# AD.net
KiCad netlist of a schematic drawn in Altium Designer
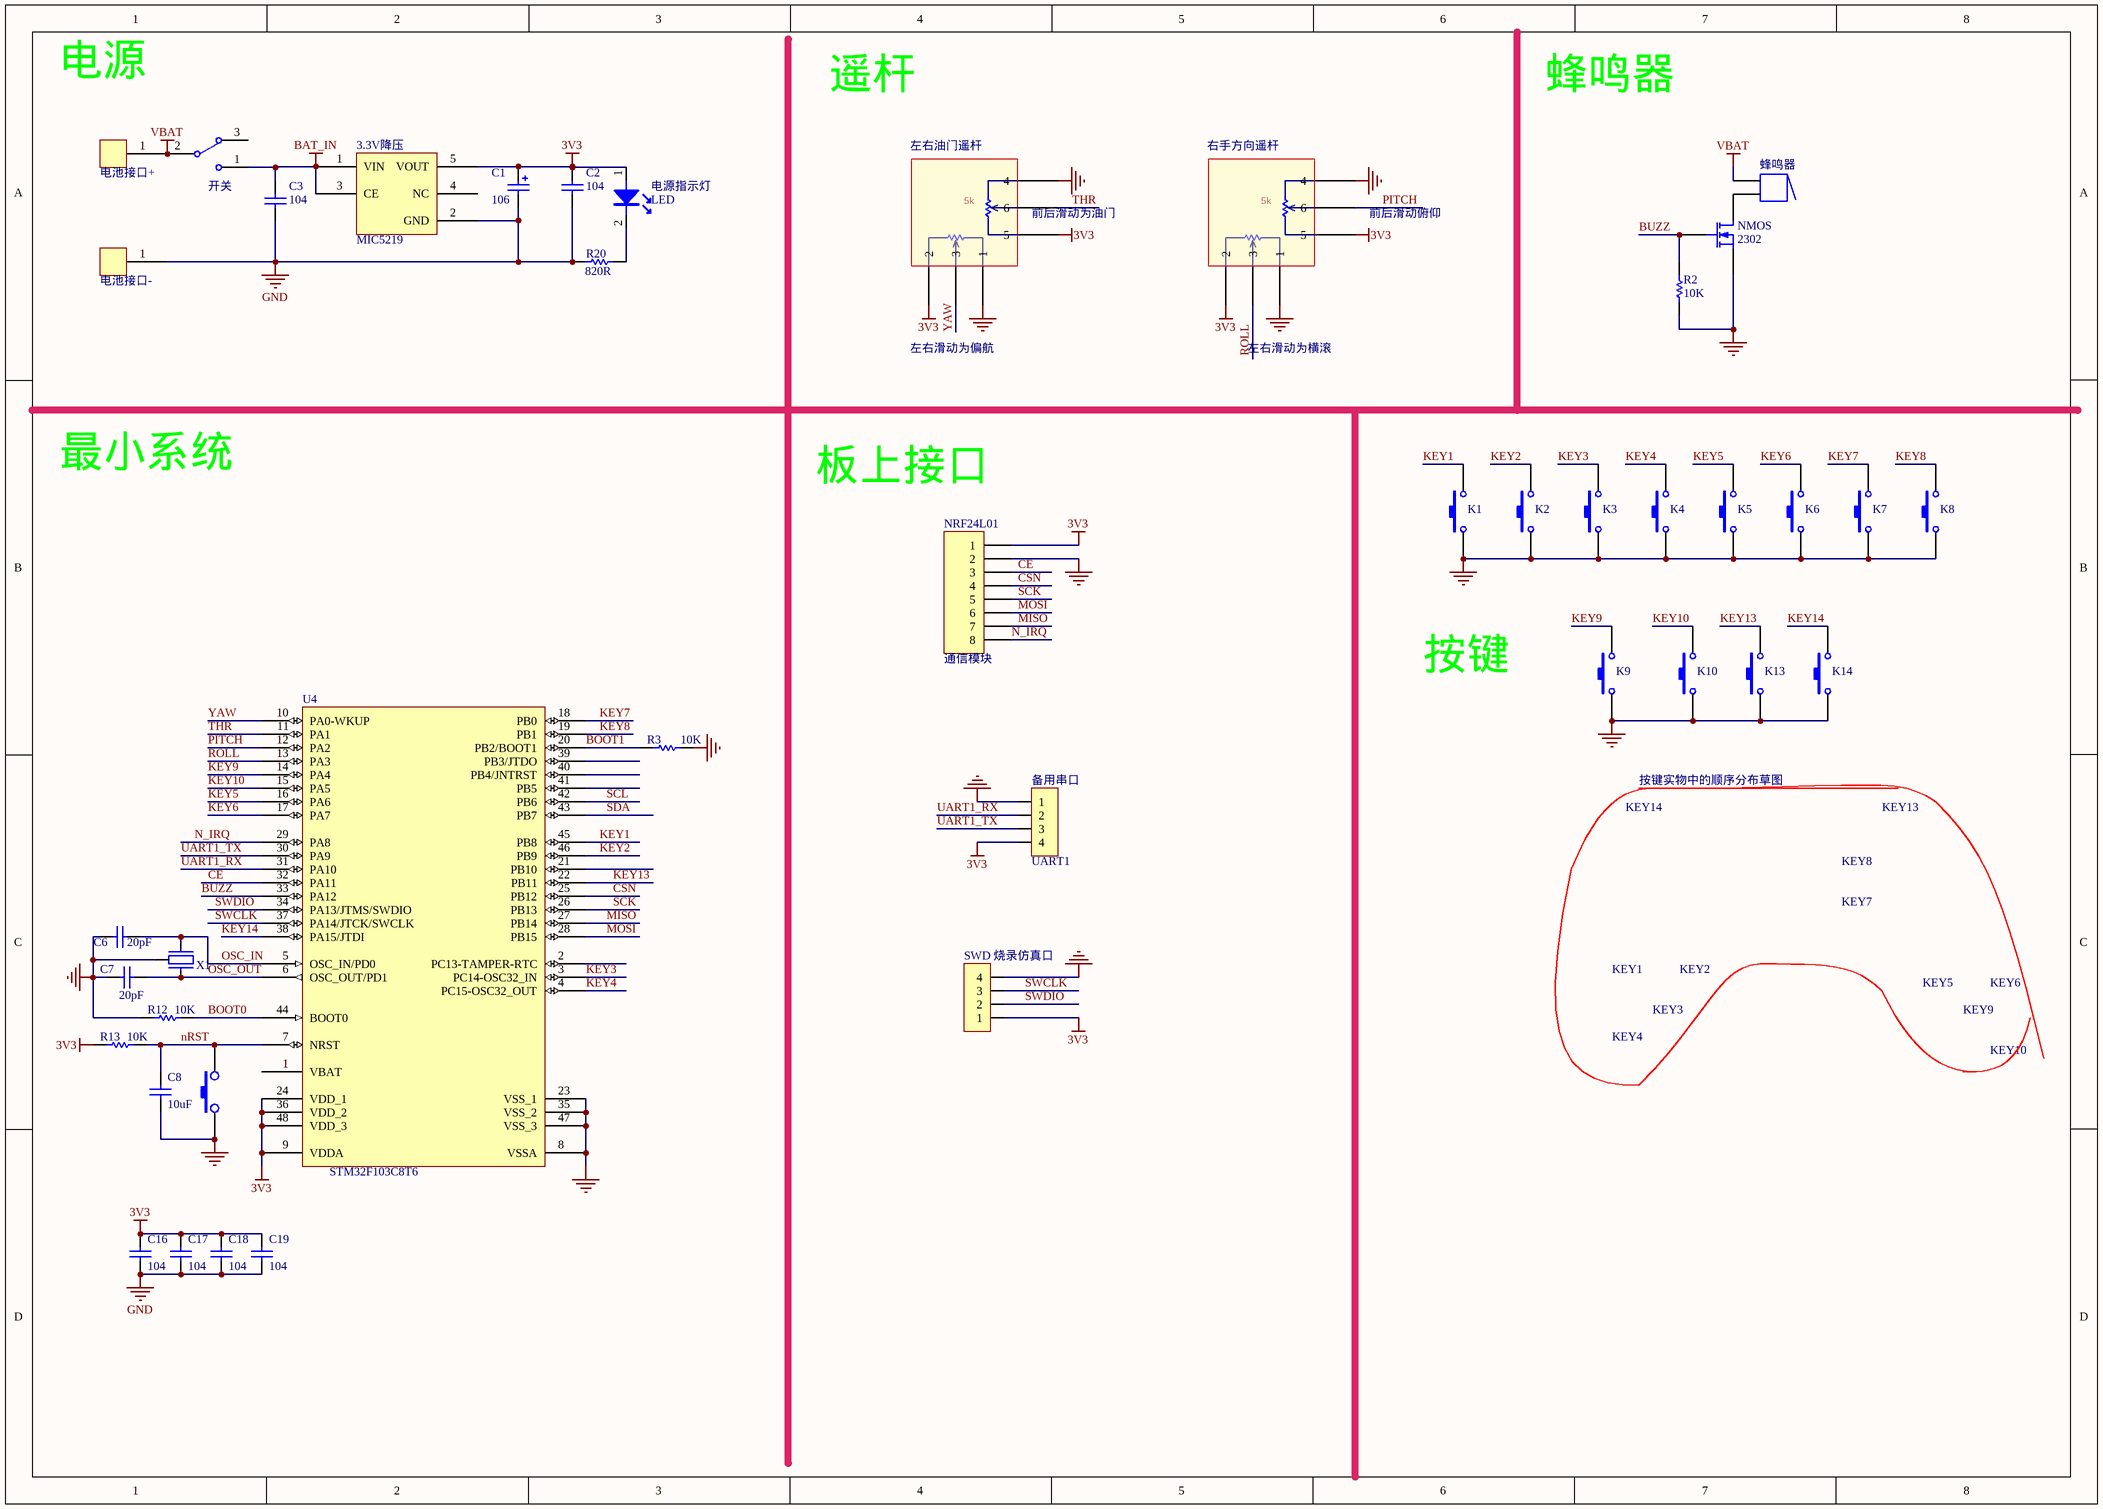
[diagram p0: 遥控原理图（AD打开）.SchDoc]

(export (version "E")
  (design (tool "Eeschema 10.0.6"))
  (components
    (comp (ref "3.3V降压")
      (value "MIC5219")
      (footprint "SOT23-5")
      (libsource (lib "quadrotor") (part "HT7X33"))
    )
    (comp (ref "C1")
      (value "106")
      (footprint "1206")
      (description "Polarized Capacitor (Radial)")
      (fields
        (field (name "VOLTAGE") "16V")
        (field (name "Comment") "Cap Tan A")
        (field (name "PUBLISHER") "Altium Limited")
      )
      (libsource (lib "ChapuIntegratedLibrary") (part "Cap Tan A"))
    )
    (comp (ref "C2")
      (value "104")
      (footprint "1206_C")
      (description "Polarized Capacitor (Radial)")
      (fields (field (name "Comment") "Cap Chip 1206") (field (name "PUBLISHER") "Altium Limited"))
      (libsource (lib "ChapuIntegratedLibrary") (part "Cap Chip 1206"))
    )
    (comp (ref "C3")
      (value "104")
      (footprint "0603_C")
      (description "Polarized Capacitor (Radial)")
      (fields (field (name "Comment") "Cap Chip 1206") (field (name "PUBLISHER") "Altium Limited"))
      (libsource (lib "ChapuIntegratedLibrary") (part "Cap Chip 1206"))
    )
    (comp (ref "C6") (value "20pF") (footprint "0603_C") (libsource (lib "1218迷你四轴工程_1") (part "C0603")))
    (comp (ref "C7") (value "20pF") (footprint "0603_C") (libsource (lib "1218迷你四轴工程_1") (part "C0603")))
    (comp (ref "C8") (value "10uF") (footprint "0603_C") (libsource (lib "1218迷你四轴工程_1") (part "C0603")))
    (comp (ref "C16") (value "104") (footprint "0603_C") (libsource (lib "1218迷你四轴工程_1") (part "C0603")))
    (comp (ref "C17") (value "104") (footprint "0603_C") (libsource (lib "1218迷你四轴工程_1") (part "C0603")))
    (comp (ref "C18") (value "104") (footprint "0603_C") (libsource (lib "1218迷你四轴工程_1") (part "C0603")))
    (comp (ref "C19") (value "104") (footprint "0603_C") (libsource (lib "1218迷你四轴工程_1") (part "C0603")))
    (comp (ref "K1")
      (value "40%（油門上限）")
      (footprint "4脚贴片点动开关")
      (description "Switch")
      (fields (field (name "PUBLISHER") "Altium Limited"))
      (libsource (lib "Miscellaneous Devices") (part "SW-PB"))
    )
    (comp (ref "K2")
      (value "60%")
      (footprint "4脚贴片点动开关")
      (description "Switch")
      (fields (field (name "PUBLISHER") "Altium Limited"))
      (libsource (lib "Miscellaneous Devices") (part "SW-PB"))
    )
    (comp (ref "K3")
      (value "40%（油門上限）")
      (footprint "4脚贴片点动开关")
      (description "Switch")
      (fields (field (name "PUBLISHER") "Altium Limited"))
      (libsource (lib "Miscellaneous Devices") (part "SW-PB"))
    )
    (comp (ref "K4")
      (value "60%")
      (footprint "4脚贴片点动开关")
      (description "Switch")
      (fields (field (name "PUBLISHER") "Altium Limited"))
      (libsource (lib "Miscellaneous Devices") (part "SW-PB"))
    )
    (comp (ref "K5")
      (value "40%（油門上限）")
      (footprint "4脚贴片点动开关")
      (description "Switch")
      (fields (field (name "PUBLISHER") "Altium Limited"))
      (libsource (lib "Miscellaneous Devices") (part "SW-PB"))
    )
    (comp (ref "K6")
      (value "60%")
      (footprint "4脚贴片点动开关")
      (description "Switch")
      (fields (field (name "PUBLISHER") "Altium Limited"))
      (libsource (lib "Miscellaneous Devices") (part "SW-PB"))
    )
    (comp (ref "K7")
      (value "40%（油門上限）")
      (footprint "4脚贴片点动开关")
      (description "Switch")
      (fields (field (name "PUBLISHER") "Altium Limited"))
      (libsource (lib "Miscellaneous Devices") (part "SW-PB"))
    )
    (comp (ref "K8")
      (value "60%")
      (footprint "4脚贴片点动开关")
      (description "Switch")
      (fields (field (name "PUBLISHER") "Altium Limited"))
      (libsource (lib "Miscellaneous Devices") (part "SW-PB"))
    )
    (comp (ref "K9")
      (value "40%（油門上限）")
      (footprint "4脚贴片点动开关")
      (description "Switch")
      (fields (field (name "PUBLISHER") "Altium Limited"))
      (libsource (lib "Miscellaneous Devices") (part "SW-PB"))
    )
    (comp (ref "K10")
      (value "60%")
      (footprint "4脚贴片点动开关")
      (description "Switch")
      (fields (field (name "PUBLISHER") "Altium Limited"))
      (libsource (lib "Miscellaneous Devices") (part "SW-PB"))
    )
    (comp (ref "K13")
      (value "40%（油門上限）")
      (footprint "侧贴侧按点动开关")
      (description "Switch")
      (fields (field (name "PUBLISHER") "Altium Limited"))
      (libsource (lib "Miscellaneous Devices") (part "SW-PB"))
    )
    (comp (ref "K14")
      (value "60%")
      (footprint "侧贴侧按点动开关")
      (description "Switch")
      (fields (field (name "PUBLISHER") "Altium Limited"))
      (libsource (lib "Miscellaneous Devices") (part "SW-PB"))
    )
    (comp (ref "NMOS")
      (value "2302")
      (footprint "SOT-23-3")
      (description "N-Channel MOSFET")
      (fields (field (name "PUBLISHER") "Altium Limited"))
      (libsource (lib "Miscellaneous Devices") (part "MOSFET-N"))
    )
    (comp (ref "NRF24L01")
      (value "通信模块")
      (footprint "HDR1X8")
      (description "Header, 8-Pin")
      (fields (field (name "PUBLISHER") "Altium Limited"))
      (libsource (lib "Miscellaneous Connectors") (part "Header 8"))
    )
    (comp (ref "R2")
      (value "10K")
      (footprint "0603_R")
      (description "Resistor")
      (fields (field (name "Comment") "222") (field (name "PUBLISHER") "Altium Limited"))
      (libsource (lib "Miscellaneous Devices") (part "Res1"))
    )
    (comp (ref "R3")
      (value "10K")
      (footprint "0603_R")
      (description "Resistor")
      (fields (field (name "Comment") "Res1") (field (name "PUBLISHER") "Altium Limited"))
      (libsource (lib "Miscellaneous Devices") (part "Res1"))
    )
    (comp (ref "R12")
      (value "10K")
      (footprint "0603_R")
      (description "Resistor")
      (fields (field (name "Comment") "Res1") (field (name "PUBLISHER") "Altium Limited"))
      (libsource (lib "Miscellaneous Devices") (part "Res1"))
    )
    (comp (ref "R13")
      (value "10K")
      (footprint "0603_R")
      (description "Resistor")
      (fields (field (name "Comment") "Res1") (field (name "PUBLISHER") "Altium Limited"))
      (libsource (lib "Miscellaneous Devices") (part "Res1"))
    )
    (comp (ref "R20")
      (value "820R")
      (footprint "0603_R")
      (description "Resistor")
      (fields (field (name "Comment") "222") (field (name "PUBLISHER") "Altium Limited"))
      (libsource (lib "Miscellaneous Devices") (part "Res1"))
    )
    (comp (ref "REST1") (value "SW-PB") (footprint "SW-2") (libsource (lib "SW开关") (part "SW-PB")))
    (comp (ref "SWD 烧录仿真口")
      (value "SWD")
      (footprint "1.27侧卧表贴")
      (description "Header, 4-Pin, Right Angle")
      (fields (field (name "PUBLISHER") "Altium Limited"))
      (libsource (lib "linch051") (part "Header 4H"))
    )
    (comp (ref "U4")
      (value "STM32F103C8T6")
      (footprint "LQFP48")
      (libsource (lib "微型四轴") (part "STM32F103C8T6"))
    )
    (comp (ref "X1") (value "XTAL_SMT") (footprint "村田陶瓷晶振") (libsource (lib "dx原理图库") (part "XTAL_SMT")))
    (comp (ref "右手方向遥杆") (value "摇杆") (footprint "遥控电位器") (libsource (lib "开源小遥控") (part "摇杆")))
    (comp (ref "备用串口")
      (value "UART1")
      (footprint "1.27侧卧表贴")
      (description "Header, 4-Pin, Right Angle")
      (fields (field (name "PUBLISHER") "Altium Limited"))
      (libsource (lib "") (part "Header 4H_1"))
    )
    (comp (ref "左右油门遥杆") (value "摇杆") (footprint "遥控电位器") (libsource (lib "开源小遥控") (part "摇杆")))
    (comp (ref "开关")
      (value "SW-SPDT")
      (footprint "SW-5")
      (description "SPDT Subminiature Toggle Switch, Right Angle Mounting, Vertical Actuation")
      (fields (field (name "PUBLISHER") "Altium Limited"))
      (libsource (lib "Miscellaneous Devices") (part "SW-SPDT"))
    )
    (comp (ref "电池接口+") (value "Header 1") (footprint "BAT") (libsource (lib "quadrotor") (part "Header 1")))
    (comp (ref "电池接口-") (value "Header 1") (footprint "BAT") (libsource (lib "quadrotor") (part "Header 1")))
    (comp (ref "电源指示灯") (value "LED") (footprint "0603_LED") (libsource (lib "1218迷你四轴工程_1") (part "LED")))
    (comp (ref "蜂鸣器")
      (value "Buzzer")
      (footprint "蜂鸣器9mm")
      (description "Magnetic Transducer Buzzer")
      (fields (field (name "PUBLISHER") "Altium Limited"))
      (libsource (lib "PCB_Project1") (part "Buzzer"))
    )
  )
  (nets
    (net (code "1") (name "/BOOT0") (class "Default")
      (node (ref "R12") (pin "1") (pinfunction "1_1") (pintype "passive"))
      (node (ref "U4") (pin "44") (pinfunction "BOOT0_44") (pintype "input"))
    )
    (net (code "2") (name "/BOOT1") (class "Default")
      (node (ref "R3") (pin "2") (pinfunction "2_2") (pintype "passive"))
      (node (ref "U4") (pin "20") (pinfunction "PB2/BOOT1_20") (pintype "bidirectional"))
    )
    (net (code "3") (name "/BUZZ") (class "Default")
      (node (ref "NMOS") (pin "2") (pinfunction "G_2") (pintype "passive"))
      (node (ref "R2") (pin "1") (pinfunction "1_1") (pintype "passive"))
      (node (ref "U4") (pin "33") (pinfunction "PA12_33") (pintype "bidirectional"))
    )
    (net (code "4") (name "/CE") (class "Default")
      (node (ref "NRF24L01") (pin "3") (pinfunction "3_3") (pintype "passive"))
      (node (ref "U4") (pin "32") (pinfunction "PA11_32") (pintype "bidirectional"))
    )
    (net (code "5") (name "/CSN") (class "Default")
      (node (ref "NRF24L01") (pin "4") (pinfunction "4_4") (pintype "passive"))
      (node (ref "U4") (pin "25") (pinfunction "PB12_25") (pintype "bidirectional"))
    )
    (net (code "6") (name "/KEY1") (class "Default")
      (node (ref "K1") (pin "2") (pinfunction "2_2") (pintype "passive"))
      (node (ref "U4") (pin "45") (pinfunction "PB8_45") (pintype "bidirectional"))
    )
    (net (code "7") (name "/KEY2") (class "Default")
      (node (ref "K2") (pin "2") (pinfunction "2_2") (pintype "passive"))
      (node (ref "U4") (pin "46") (pinfunction "PB9_46") (pintype "bidirectional"))
    )
    (net (code "8") (name "/KEY3") (class "Default")
      (node (ref "K3") (pin "2") (pinfunction "2_2") (pintype "passive"))
      (node (ref "U4") (pin "3") (pinfunction "PC14-OSC32_IN_3") (pintype "bidirectional"))
    )
    (net (code "9") (name "/KEY4") (class "Default")
      (node (ref "K4") (pin "2") (pinfunction "2_2") (pintype "passive"))
      (node (ref "U4") (pin "4") (pinfunction "PC15-OSC32_OUT_4") (pintype "bidirectional"))
    )
    (net (code "10") (name "/KEY5") (class "Default")
      (node (ref "K5") (pin "2") (pinfunction "2_2") (pintype "passive"))
      (node (ref "U4") (pin "16") (pinfunction "PA6_16") (pintype "bidirectional"))
    )
    (net (code "11") (name "/KEY6") (class "Default")
      (node (ref "K6") (pin "2") (pinfunction "2_2") (pintype "passive"))
      (node (ref "U4") (pin "17") (pinfunction "PA7_17") (pintype "bidirectional"))
    )
    (net (code "12") (name "/KEY7") (class "Default")
      (node (ref "K7") (pin "2") (pinfunction "2_2") (pintype "passive"))
      (node (ref "U4") (pin "18") (pinfunction "PB0_18") (pintype "bidirectional"))
    )
    (net (code "13") (name "/KEY8") (class "Default")
      (node (ref "K8") (pin "2") (pinfunction "2_2") (pintype "passive"))
      (node (ref "U4") (pin "19") (pinfunction "PB1_19") (pintype "bidirectional"))
    )
    (net (code "14") (name "/KEY9") (class "Default")
      (node (ref "K9") (pin "2") (pinfunction "2_2") (pintype "passive"))
      (node (ref "U4") (pin "14") (pinfunction "PA4_14") (pintype "bidirectional"))
    )
    (net (code "15") (name "/KEY10") (class "Default")
      (node (ref "K10") (pin "2") (pinfunction "2_2") (pintype "passive"))
      (node (ref "U4") (pin "15") (pinfunction "PA5_15") (pintype "bidirectional"))
    )
    (net (code "16") (name "/KEY13") (class "Default")
      (node (ref "K13") (pin "2") (pinfunction "2_2") (pintype "passive"))
      (node (ref "U4") (pin "22") (pinfunction "PB11_22") (pintype "bidirectional"))
    )
    (net (code "17") (name "/KEY14") (class "Default")
      (node (ref "K14") (pin "2") (pinfunction "2_2") (pintype "passive"))
      (node (ref "U4") (pin "38") (pinfunction "PA15/JTDI_38") (pintype "bidirectional"))
    )
    (net (code "18") (name "/MISO") (class "Default")
      (node (ref "NRF24L01") (pin "7") (pinfunction "7_7") (pintype "passive"))
      (node (ref "U4") (pin "27") (pinfunction "PB14_27") (pintype "bidirectional"))
    )
    (net (code "19") (name "/MOSI") (class "Default")
      (node (ref "NRF24L01") (pin "6") (pinfunction "6_6") (pintype "passive"))
      (node (ref "U4") (pin "28") (pinfunction "PB15_28") (pintype "bidirectional"))
    )
    (net (code "20") (name "/N_IRQ") (class "Default")
      (node (ref "NRF24L01") (pin "8") (pinfunction "8_8") (pintype "passive"))
      (node (ref "U4") (pin "29") (pinfunction "PA8_29") (pintype "bidirectional"))
    )
    (net (code "21") (name "/OSC_IN") (class "Default")
      (node (ref "C6") (pin "1") (pinfunction "1_1") (pintype "passive"))
      (node (ref "U4") (pin "5") (pinfunction "OSC_IN/PD0_5") (pintype "input"))
      (node (ref "X1") (pin "2") (pintype "passive"))
    )
    (net (code "22") (name "/OSC_OUT") (class "Default")
      (node (ref "C7") (pin "1") (pinfunction "1_1") (pintype "passive"))
      (node (ref "U4") (pin "6") (pinfunction "OSC_OUT/PD1_6") (pintype "output"))
      (node (ref "X1") (pin "1") (pintype "passive"))
    )
    (net (code "23") (name "/PITCH") (class "Default")
      (node (ref "U4") (pin "12") (pinfunction "PA2_12") (pintype "bidirectional"))
      (node (ref "右手方向遥杆") (pin "6") (pinfunction "6_6") (pintype "passive"))
    )
    (net (code "24") (name "/ROLL") (class "Default")
      (node (ref "U4") (pin "13") (pinfunction "PA3_13") (pintype "bidirectional"))
      (node (ref "右手方向遥杆") (pin "3") (pinfunction "3_3") (pintype "passive"))
    )
    (net (code "25") (name "/SCK") (class "Default")
      (node (ref "NRF24L01") (pin "5") (pinfunction "5_5") (pintype "passive"))
      (node (ref "U4") (pin "26") (pinfunction "PB13_26") (pintype "bidirectional"))
    )
    (net (code "26") (name "/SCL") (class "Default")
      (node (ref "U4") (pin "42") (pinfunction "PB6_42") (pintype "bidirectional"))
    )
    (net (code "27") (name "/SDA") (class "Default")
      (node (ref "U4") (pin "43") (pinfunction "PB7_43") (pintype "bidirectional"))
    )
    (net (code "28") (name "/SWCLK") (class "Default")
      (node (ref "SWD 烧录仿真口") (pin "3") (pinfunction "3_3") (pintype "passive"))
      (node (ref "U4") (pin "37") (pinfunction "PA14/JTCK/SWCLK_37") (pintype "bidirectional"))
    )
    (net (code "29") (name "/SWDIO") (class "Default")
      (node (ref "SWD 烧录仿真口") (pin "2") (pinfunction "2_2") (pintype "passive"))
      (node (ref "U4") (pin "34") (pinfunction "PA13/JTMS/SWDIO_34") (pintype "bidirectional"))
    )
    (net (code "30") (name "/THR") (class "Default")
      (node (ref "U4") (pin "11") (pinfunction "PA1_11") (pintype "bidirectional"))
      (node (ref "左右油门遥杆") (pin "6") (pinfunction "6_6") (pintype "passive"))
    )
    (net (code "31") (name "/UART1_RX") (class "Default")
      (node (ref "U4") (pin "31") (pinfunction "PA10_31") (pintype "bidirectional"))
      (node (ref "备用串口") (pin "2") (pinfunction "2_2") (pintype "passive"))
    )
    (net (code "32") (name "/UART1_TX") (class "Default")
      (node (ref "U4") (pin "30") (pinfunction "PA9_30") (pintype "bidirectional"))
      (node (ref "备用串口") (pin "3") (pinfunction "3_3") (pintype "passive"))
    )
    (net (code "33") (name "/YAW") (class "Default")
      (node (ref "U4") (pin "10") (pinfunction "PA0-WKUP_10") (pintype "bidirectional"))
      (node (ref "左右油门遥杆") (pin "3") (pinfunction "3_3") (pintype "passive"))
    )
    (net (code "34") (name "/nRST") (class "Default")
      (node (ref "C8") (pin "1") (pinfunction "1_1") (pintype "passive"))
      (node (ref "R13") (pin "1") (pinfunction "1_1") (pintype "passive"))
      (node (ref "REST1") (pin "2") (pinfunction "2_2") (pintype "passive"))
      (node (ref "U4") (pin "7") (pinfunction "NRST_7") (pintype "bidirectional"))
    )
    (net (code "35") (name "3V3") (class "Default")
      (node (ref "3.3V降压") (pin "5") (pinfunction "VOUT_5") (pintype "passive"))
      (node (ref "C1") (pin "2") (pinfunction "1_2") (pintype "passive"))
      (node (ref "C16") (pin "1") (pinfunction "1_1") (pintype "passive"))
      (node (ref "C17") (pin "1") (pinfunction "1_1") (pintype "passive"))
      (node (ref "C18") (pin "1") (pinfunction "1_1") (pintype "passive"))
      (node (ref "C19") (pin "1") (pinfunction "1_1") (pintype "passive"))
      (node (ref "C2") (pin "1") (pinfunction "1_1") (pintype "passive"))
      (node (ref "NRF24L01") (pin "1") (pinfunction "1_1") (pintype "passive"))
      (node (ref "R13") (pin "2") (pinfunction "2_2") (pintype "passive"))
      (node (ref "SWD 烧录仿真口") (pin "1") (pinfunction "1_1") (pintype "passive"))
      (node (ref "U4") (pin "24") (pinfunction "VDD_1_24") (pintype "power_in"))
      (node (ref "U4") (pin "36") (pinfunction "VDD_2_36") (pintype "power_in"))
      (node (ref "U4") (pin "48") (pinfunction "VDD_3_48") (pintype "power_in"))
      (node (ref "U4") (pin "9") (pinfunction "VDDA_9") (pintype "power_in"))
      (node (ref "右手方向遥杆") (pin "2") (pinfunction "2_2") (pintype "passive"))
      (node (ref "右手方向遥杆") (pin "5") (pinfunction "5_5") (pintype "passive"))
      (node (ref "备用串口") (pin "4") (pinfunction "4_4") (pintype "passive"))
      (node (ref "左右油门遥杆") (pin "2") (pinfunction "2_2") (pintype "passive"))
      (node (ref "左右油门遥杆") (pin "5") (pinfunction "5_5") (pintype "passive"))
      (node (ref "电源指示灯") (pin "1") (pinfunction "1_1") (pintype "passive"))
    )
    (net (code "36") (name "BAT_IN") (class "Default")
      (node (ref "3.3V降压") (pin "1") (pinfunction "VIN_1") (pintype "passive"))
      (node (ref "3.3V降压") (pin "3") (pinfunction "CE_3") (pintype "passive"))
      (node (ref "C3") (pin "1") (pinfunction "1_1") (pintype "passive"))
      (node (ref "开关") (pin "1") (pinfunction "1_1") (pintype "passive"))
    )
    (net (code "37") (name "GND") (class "Default")
      (node (ref "3.3V降压") (pin "2") (pinfunction "GND_2") (pintype "passive"))
      (node (ref "C1") (pin "1") (pinfunction "2_1") (pintype "passive"))
      (node (ref "C16") (pin "2") (pinfunction "2_2") (pintype "passive"))
      (node (ref "C17") (pin "2") (pinfunction "2_2") (pintype "passive"))
      (node (ref "C18") (pin "2") (pinfunction "2_2") (pintype "passive"))
      (node (ref "C19") (pin "2") (pinfunction "2_2") (pintype "passive"))
      (node (ref "C2") (pin "2") (pinfunction "2_2") (pintype "passive"))
      (node (ref "C3") (pin "2") (pinfunction "2_2") (pintype "passive"))
      (node (ref "C6") (pin "2") (pinfunction "2_2") (pintype "passive"))
      (node (ref "C7") (pin "2") (pinfunction "2_2") (pintype "passive"))
      (node (ref "C8") (pin "2") (pinfunction "2_2") (pintype "passive"))
      (node (ref "K1") (pin "1") (pinfunction "1_1") (pintype "passive"))
      (node (ref "K10") (pin "1") (pinfunction "1_1") (pintype "passive"))
      (node (ref "K13") (pin "1") (pinfunction "1_1") (pintype "passive"))
      (node (ref "K14") (pin "1") (pinfunction "1_1") (pintype "passive"))
      (node (ref "K2") (pin "1") (pinfunction "1_1") (pintype "passive"))
      (node (ref "K3") (pin "1") (pinfunction "1_1") (pintype "passive"))
      (node (ref "K4") (pin "1") (pinfunction "1_1") (pintype "passive"))
      (node (ref "K5") (pin "1") (pinfunction "1_1") (pintype "passive"))
      (node (ref "K6") (pin "1") (pinfunction "1_1") (pintype "passive"))
      (node (ref "K7") (pin "1") (pinfunction "1_1") (pintype "passive"))
      (node (ref "K8") (pin "1") (pinfunction "1_1") (pintype "passive"))
      (node (ref "K9") (pin "1") (pinfunction "1_1") (pintype "passive"))
      (node (ref "NMOS") (pin "3") (pinfunction "S_3") (pintype "passive"))
      (node (ref "NRF24L01") (pin "2") (pinfunction "2_2") (pintype "passive"))
      (node (ref "R12") (pin "2") (pinfunction "2_2") (pintype "passive"))
      (node (ref "R2") (pin "2") (pinfunction "2_2") (pintype "passive"))
      (node (ref "R20") (pin "1") (pinfunction "1_1") (pintype "passive"))
      (node (ref "R3") (pin "1") (pinfunction "1_1") (pintype "passive"))
      (node (ref "REST1") (pin "1") (pinfunction "1_1") (pintype "passive"))
      (node (ref "SWD 烧录仿真口") (pin "4") (pinfunction "4_4") (pintype "passive"))
      (node (ref "U4") (pin "23") (pinfunction "VSS_1_23") (pintype "power_in"))
      (node (ref "U4") (pin "35") (pinfunction "VSS_2_35") (pintype "power_in"))
      (node (ref "U4") (pin "47") (pinfunction "VSS_3_47") (pintype "power_in"))
      (node (ref "U4") (pin "8") (pinfunction "VSSA_8") (pintype "power_in"))
      (node (ref "X1") (pin "0") (pinfunction "0_0") (pintype "passive"))
      (node (ref "右手方向遥杆") (pin "1") (pinfunction "1_1") (pintype "passive"))
      (node (ref "右手方向遥杆") (pin "4") (pinfunction "4_4") (pintype "passive"))
      (node (ref "备用串口") (pin "1") (pinfunction "1_1") (pintype "passive"))
      (node (ref "左右油门遥杆") (pin "1") (pinfunction "1_1") (pintype "passive"))
      (node (ref "左右油门遥杆") (pin "4") (pinfunction "4_4") (pintype "passive"))
      (node (ref "电池接口-") (pin "1") (pintype "passive"))
    )
    (net (code "38") (name "Net-(NMOS-D)") (class "Default")
      (node (ref "NMOS") (pin "1") (pinfunction "D_1") (pintype "passive"))
      (node (ref "蜂鸣器") (pin "1") (pinfunction "1_1") (pintype "passive"))
    )
    (net (code "39") (name "Net-(R20-Pad2)") (class "Default")
      (node (ref "R20") (pin "2") (pinfunction "2_2") (pintype "passive"))
      (node (ref "电源指示灯") (pin "2") (pinfunction "2_2") (pintype "passive"))
    )
    (net (code "40") (name "VBAT") (class "Default")
      (node (ref "开关") (pin "2") (pinfunction "2_2") (pintype "passive"))
      (node (ref "电池接口+") (pin "1") (pintype "passive"))
      (node (ref "蜂鸣器") (pin "2") (pinfunction "2_2") (pintype "passive"))
    )
    (net (code "41") (name "unconnected-(3.3V降压-NC-Pad4)") (class "Default")
      (node (ref "3.3V降压") (pin "4") (pinfunction "NC_4") (pintype "passive"))
    )
    (net (code "42") (name "unconnected-(U4-PB3{slash}JTDO-Pad39)") (class "Default")
      (node (ref "U4") (pin "39") (pinfunction "PB3/JTDO_39") (pintype "bidirectional"))
    )
    (net (code "43") (name "unconnected-(U4-PB4{slash}JNTRST-Pad40)") (class "Default")
      (node (ref "U4") (pin "40") (pinfunction "PB4/JNTRST_40") (pintype "bidirectional"))
    )
    (net (code "44") (name "unconnected-(U4-PB5-Pad41)") (class "Default")
      (node (ref "U4") (pin "41") (pinfunction "PB5_41") (pintype "bidirectional"))
    )
    (net (code "45") (name "unconnected-(U4-PB10-Pad21)") (class "Default")
      (node (ref "U4") (pin "21") (pinfunction "PB10_21") (pintype "bidirectional"))
    )
    (net (code "46") (name "unconnected-(U4-PC13-TAMPER-RTC-Pad2)") (class "Default")
      (node (ref "U4") (pin "2") (pinfunction "PC13-TAMPER-RTC_2") (pintype "bidirectional"))
    )
    (net (code "47") (name "unconnected-(U4-VBAT-Pad1)") (class "Default")
      (node (ref "U4") (pin "1") (pinfunction "VBAT_1") (pintype "power_in"))
    )
    (net (code "48") (name "unconnected-(开关-Pad3)") (class "Default")
      (node (ref "开关") (pin "3") (pinfunction "3_3") (pintype "passive"))
    )
  )
)
